# Design1.net
KiCad netlist of a schematic drawn in EAGLE
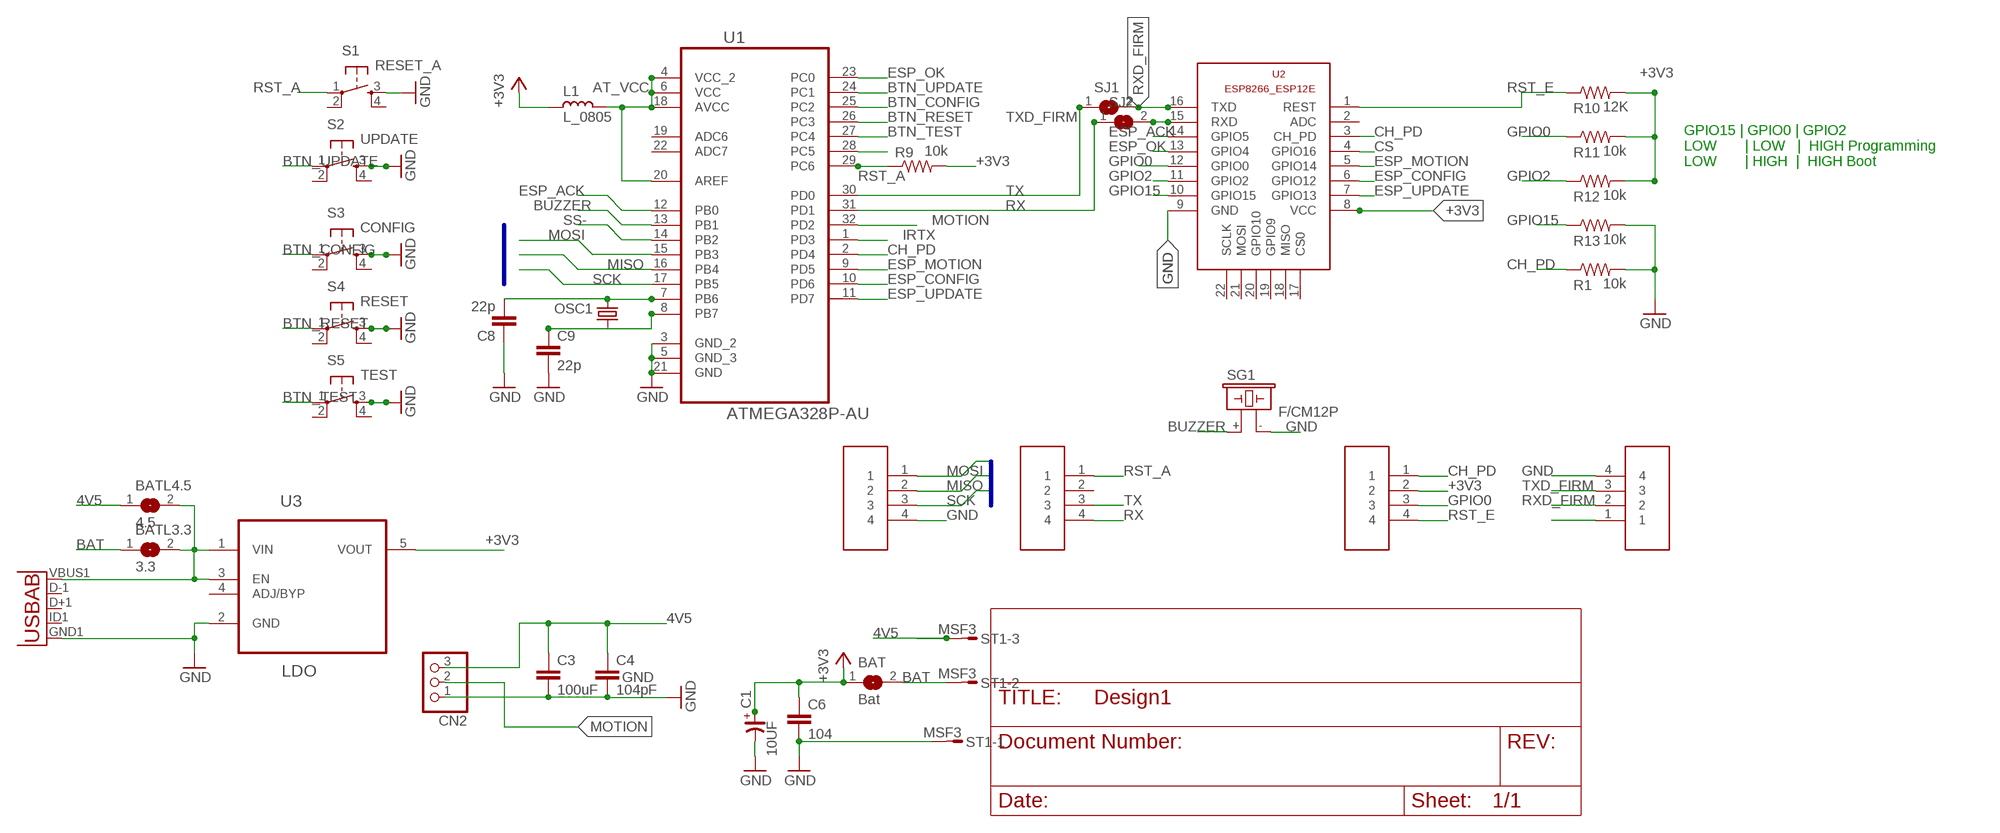
[diagram p0: schematic, sheet 1]

(export (version "E")
  (design (tool "Eeschema 10.0.6"))
  (components
    (comp (ref "BAT")
      (value "Bat")
      (footprint "eagle-import:SJ")
      (libsource (lib "eagle-import") (part "SJ"))
    )
    (comp (ref "BATL3.3")
      (value "3.3")
      (footprint "eagle-import:SJ")
      (libsource (lib "eagle-import") (part "SJ"))
    )
    (comp (ref "BATL4.5")
      (value "4.5")
      (footprint "eagle-import:SJ")
      (libsource (lib "eagle-import") (part "SJ"))
    )
    (comp (ref "C1")
      (value "10UF")
      (footprint "eagle-import:C6032_T")
      (libsource (lib "eagle-import") (part "CP_6032"))
    )
    (comp (ref "C3")
      (value "100uF")
      (footprint "eagle-import:C0805")
      (libsource (lib "eagle-import") (part "C-EUC0805"))
    )
    (comp (ref "C4")
      (value "104pF")
      (footprint "eagle-import:C0805")
      (libsource (lib "eagle-import") (part "C-EUC0805"))
    )
    (comp (ref "C6")
      (value "104")
      (footprint "eagle-import:C0805")
      (libsource (lib "eagle-import") (part "C-EUC0805"))
    )
    (comp (ref "C8")
      (value "22p")
      (footprint "eagle-import:C0805K")
      (libsource (lib "eagle-import") (part "C-EUC0805K"))
    )
    (comp (ref "C9")
      (value "22p")
      (footprint "eagle-import:C0805K")
      (libsource (lib "eagle-import") (part "C-EUC0805K"))
    )
    (comp (ref "CN1")
      (value "USB\"\"")
      (footprint "eagle-import:USB-MICRO-SMD")
      (libsource (lib "eagle-import") (part "USB{dblquote}{dblquote}"))
    )
    (comp (ref "CN2")
      (value "PINHD-1X3")
      (footprint "eagle-import:1X03")
      (libsource (lib "eagle-import") (part "PINHD-1X3"))
    )
    (comp (ref "CON1")
      (value "AT1")
      (footprint "eagle-import:FIRM_PADS")
      (libsource (lib "eagle-import") (part "FIRM_PADSSMD_FIRM_PADS"))
    )
    (comp (ref "CON2")
      (value "AT2")
      (footprint "eagle-import:FIRM_PADS")
      (libsource (lib "eagle-import") (part "FIRM_PADSSMD_FIRM_PADS"))
    )
    (comp (ref "CON3")
      (value "ESP1")
      (footprint "eagle-import:FIRM_PADS")
      (libsource (lib "eagle-import") (part "FIRM_PADSSMD_FIRM_PADS"))
    )
    (comp (ref "CON4")
      (value "ESP2")
      (footprint "eagle-import:FIRM_PADS")
      (libsource (lib "eagle-import") (part "FIRM_PADSSMD_FIRM_PADS"))
    )
    (comp (ref "L1")
      (value "L_0805")
      (footprint "eagle-import:L0805")
      (libsource (lib "eagle-import") (part "L_0805"))
    )
    (comp (ref "OSC1")
      (value "CRYSTALSM49")
      (footprint "eagle-import:SM49")
      (libsource (lib "eagle-import") (part "CRYSTALSM49"))
    )
    (comp (ref "R1")
      (value "10k")
      (footprint "eagle-import:0805")
      (libsource (lib "eagle-import") (part "0.75OHM-1/4W-1%(0805)"))
    )
    (comp (ref "R9")
      (value "10k")
      (footprint "eagle-import:0805")
      (libsource (lib "eagle-import") (part "0.75OHM-1/4W-1%(0805)"))
    )
    (comp (ref "R10")
      (value "12K")
      (footprint "eagle-import:0805")
      (libsource (lib "eagle-import") (part "0.75OHM-1/4W-1%(0805)"))
    )
    (comp (ref "R11")
      (value "10k")
      (footprint "eagle-import:0805")
      (libsource (lib "eagle-import") (part "0.75OHM-1/4W-1%(0805)"))
    )
    (comp (ref "R12")
      (value "10k")
      (footprint "eagle-import:0805")
      (libsource (lib "eagle-import") (part "0.75OHM-1/4W-1%(0805)"))
    )
    (comp (ref "R13")
      (value "10k")
      (footprint "eagle-import:0805")
      (libsource (lib "eagle-import") (part "0.75OHM-1/4W-1%(0805)"))
    )
    (comp (ref "S1")
      (value "RESET_A")
      (footprint "eagle-import:DTSM-6")
      (libsource (lib "eagle-import") (part "DTSM-6"))
    )
    (comp (ref "S2")
      (value "UPDATE")
      (footprint "eagle-import:DTSM-6")
      (libsource (lib "eagle-import") (part "DTSM-6"))
    )
    (comp (ref "S3")
      (value "CONFIG")
      (footprint "eagle-import:DTSM-6")
      (libsource (lib "eagle-import") (part "DTSM-6"))
    )
    (comp (ref "S4")
      (value "RESET")
      (footprint "eagle-import:DTSM-6")
      (libsource (lib "eagle-import") (part "DTSM-6"))
    )
    (comp (ref "S5")
      (value "TEST")
      (footprint "eagle-import:DTSM-6")
      (libsource (lib "eagle-import") (part "DTSM-6"))
    )
    (comp (ref "SG1")
      (value "F/CM12P")
      (footprint "eagle-import:F_CM12P")
      (libsource (lib "eagle-import") (part "F/CM12P"))
    )
    (comp (ref "SJ1") (value "SJ") (footprint "eagle-import:SJ") (libsource (lib "eagle-import") (part "SJ")))
    (comp (ref "SJ2") (value "SJ") (footprint "eagle-import:SJ") (libsource (lib "eagle-import") (part "SJ")))
    (comp (ref "ST1")
      (value "MSF3")
      (footprint "eagle-import:MSF3")
      (libsource (lib "eagle-import") (part "MSF3"))
    )
    (comp (ref "U1")
      (value "ATMEGA328P-AU")
      (footprint "eagle-import:QFP80P900X900X120-32N")
      (libsource (lib "eagle-import") (part "ATMEGA328P-AU"))
    )
    (comp (ref "U2")
      (value "ESP8266-12EESP8266-ESP12E")
      (footprint "eagle-import:ESP8266-ESP12E")
      (libsource (lib "eagle-import") (part "ESP8266-12EESP8266-ESP12E"))
    )
    (comp (ref "U3")
      (value "LDO")
      (footprint "eagle-import:SOT95P280X145-5N")
      (libsource (lib "eagle-import") (part "SPX3819M5-L-3-3"))
    )
  )
  (nets
    (net (code "2") (name "+3V3") (class "Default")
      (node (ref "BAT") (pin "1") (pinfunction "1_1") (pintype "passive"))
      (node (ref "C1") (pin "+") (pinfunction "+_+") (pintype "passive"))
      (node (ref "C6") (pin "1") (pinfunction "1_1") (pintype "passive"))
      (node (ref "CON3") (pin "2") (pinfunction "2_2") (pintype "bidirectional"))
      (node (ref "L1") (pin "2") (pinfunction "2_2") (pintype "passive"))
      (node (ref "R10") (pin "2") (pinfunction "2_2") (pintype "passive"))
      (node (ref "R11") (pin "2") (pinfunction "2_2") (pintype "passive"))
      (node (ref "R12") (pin "2") (pinfunction "2_2") (pintype "passive"))
      (node (ref "R9") (pin "2") (pinfunction "2_2") (pintype "passive"))
      (node (ref "U2") (pin "8") (pinfunction "VCC_8") (pintype "bidirectional"))
      (node (ref "U3") (pin "5") (pinfunction "VOUT_5") (pintype "output"))
    )
    (net (code "3") (name "/4V5") (class "Default")
      (node (ref "BATL4.5") (pin "1") (pinfunction "1_1") (pintype "passive"))
      (node (ref "C3") (pin "1") (pinfunction "1_1") (pintype "passive"))
      (node (ref "C4") (pin "1") (pinfunction "1_1") (pintype "passive"))
      (node (ref "CN2") (pin "3") (pinfunction "3_3") (pintype "passive"))
      (node (ref "ST1") (pin "3") (pinfunction "S_3") (pintype "passive"))
    )
    (net (code "4") (name "/AT_VCC") (class "Default")
      (node (ref "L1") (pin "1") (pinfunction "1_1") (pintype "passive"))
      (node (ref "U1") (pin "18") (pinfunction "AVCC_18") (pintype "power_in"))
      (node (ref "U1") (pin "20") (pinfunction "AREF_20") (pintype "input"))
      (node (ref "U1") (pin "4") (pinfunction "VCC_2_4") (pintype "power_in"))
      (node (ref "U1") (pin "6") (pinfunction "VCC_6") (pintype "power_in"))
    )
    (net (code "5") (name "/BAT") (class "Default")
      (node (ref "BAT") (pin "2") (pinfunction "2_2") (pintype "passive"))
      (node (ref "BATL3.3") (pin "1") (pinfunction "1_1") (pintype "passive"))
      (node (ref "ST1") (pin "2") (pinfunction "S_2") (pintype "passive"))
    )
    (net (code "6") (name "/BTN_CONFIG") (class "Default")
      (node (ref "S3") (pin "1") (pinfunction "1_1") (pintype "passive"))
      (node (ref "U1") (pin "25") (pinfunction "PC2_25") (pintype "bidirectional"))
    )
    (net (code "7") (name "/BTN_RESET") (class "Default")
      (node (ref "S4") (pin "1") (pinfunction "1_1") (pintype "passive"))
      (node (ref "U1") (pin "26") (pinfunction "PC3_26") (pintype "bidirectional"))
    )
    (net (code "8") (name "/BTN_TEST") (class "Default")
      (node (ref "S5") (pin "1") (pinfunction "1_1") (pintype "passive"))
      (node (ref "U1") (pin "27") (pinfunction "PC4_27") (pintype "bidirectional"))
    )
    (net (code "9") (name "/BTN_UPDATE") (class "Default")
      (node (ref "S2") (pin "1") (pinfunction "1_1") (pintype "passive"))
      (node (ref "U1") (pin "24") (pinfunction "PC1_24") (pintype "bidirectional"))
    )
    (net (code "10") (name "/BUZZER") (class "Default")
      (node (ref "SG1") (pin "+") (pinfunction "1_+") (pintype "passive"))
      (node (ref "U1") (pin "13") (pinfunction "PB1_13") (pintype "bidirectional"))
    )
    (net (code "11") (name "/CH_PD") (class "Default")
      (node (ref "CON3") (pin "1") (pinfunction "1_1") (pintype "bidirectional"))
      (node (ref "R1") (pin "1") (pinfunction "1_1") (pintype "passive"))
      (node (ref "U1") (pin "2") (pinfunction "PD4_2") (pintype "bidirectional"))
      (node (ref "U2") (pin "3") (pinfunction "CH_PD_3") (pintype "bidirectional"))
    )
    (net (code "12") (name "/CS") (class "Default")
      (node (ref "U2") (pin "4") (pinfunction "GPIO16_4") (pintype "bidirectional"))
    )
    (net (code "13") (name "/ESP_ACK") (class "Default")
      (node (ref "U1") (pin "12") (pinfunction "PB0_12") (pintype "bidirectional"))
      (node (ref "U2") (pin "14") (pinfunction "GPIO5_14") (pintype "bidirectional"))
    )
    (net (code "14") (name "/ESP_CONFIG") (class "Default")
      (node (ref "U1") (pin "10") (pinfunction "PD6_10") (pintype "bidirectional"))
      (node (ref "U2") (pin "6") (pinfunction "GPIO12_6") (pintype "bidirectional"))
    )
    (net (code "15") (name "/ESP_MOTION") (class "Default")
      (node (ref "U1") (pin "9") (pinfunction "PD5_9") (pintype "bidirectional"))
      (node (ref "U2") (pin "5") (pinfunction "GPIO14_5") (pintype "bidirectional"))
    )
    (net (code "16") (name "/ESP_OK") (class "Default")
      (node (ref "U1") (pin "23") (pinfunction "PC0_23") (pintype "bidirectional"))
      (node (ref "U2") (pin "13") (pinfunction "GPIO4_13") (pintype "bidirectional"))
    )
    (net (code "17") (name "/ESP_UPDATE") (class "Default")
      (node (ref "U1") (pin "11") (pinfunction "PD7_11") (pintype "bidirectional"))
      (node (ref "U2") (pin "7") (pinfunction "GPIO13_7") (pintype "bidirectional"))
    )
    (net (code "18") (name "/GPIO0") (class "Default")
      (node (ref "CON3") (pin "3") (pinfunction "3_3") (pintype "bidirectional"))
      (node (ref "R11") (pin "1") (pinfunction "1_1") (pintype "passive"))
      (node (ref "U2") (pin "12") (pinfunction "GPIO0_12") (pintype "bidirectional"))
    )
    (net (code "19") (name "/GPIO2") (class "Default")
      (node (ref "R12") (pin "1") (pinfunction "1_1") (pintype "passive"))
      (node (ref "U2") (pin "11") (pinfunction "GPIO2_11") (pintype "bidirectional"))
    )
    (net (code "20") (name "/GPIO15") (class "Default")
      (node (ref "R13") (pin "1") (pinfunction "1_1") (pintype "passive"))
      (node (ref "U2") (pin "10") (pinfunction "GPIO15_10") (pintype "bidirectional"))
    )
    (net (code "21") (name "/IRTX") (class "Default")
      (node (ref "U1") (pin "1") (pinfunction "PD3_1") (pintype "bidirectional"))
    )
    (net (code "22") (name "/ISP") (class "Default")
      (node (ref "CON1") (pin "1") (pinfunction "1_1") (pintype "bidirectional"))
      (node (ref "U1") (pin "15") (pinfunction "PB3_15") (pintype "bidirectional"))
    )
    (net (code "23") (name "/MISO") (class "Default")
      (node (ref "CON1") (pin "2") (pinfunction "2_2") (pintype "bidirectional"))
      (node (ref "U1") (pin "16") (pinfunction "PB4_16") (pintype "bidirectional"))
    )
    (net (code "24") (name "/RST_A") (class "Default")
      (node (ref "CON2") (pin "1") (pinfunction "1_1") (pintype "bidirectional"))
      (node (ref "R9") (pin "1") (pinfunction "1_1") (pintype "passive"))
      (node (ref "S1") (pin "1") (pinfunction "1_1") (pintype "passive"))
      (node (ref "U1") (pin "29") (pinfunction "PC6_29") (pintype "bidirectional"))
    )
    (net (code "25") (name "/RST_E") (class "Default")
      (node (ref "CON3") (pin "4") (pinfunction "4_4") (pintype "bidirectional"))
      (node (ref "R10") (pin "1") (pinfunction "1_1") (pintype "passive"))
      (node (ref "U2") (pin "1") (pinfunction "REST_1") (pintype "bidirectional"))
    )
    (net (code "26") (name "/RX") (class "Default")
      (node (ref "CON2") (pin "4") (pinfunction "4_4") (pintype "bidirectional"))
      (node (ref "SJ2") (pin "1") (pinfunction "1_1") (pintype "passive"))
      (node (ref "U1") (pin "31") (pinfunction "PD1_31") (pintype "bidirectional"))
    )
    (net (code "27") (name "/SCK") (class "Default")
      (node (ref "CON1") (pin "3") (pinfunction "3_3") (pintype "bidirectional"))
      (node (ref "U1") (pin "17") (pinfunction "PB5_17") (pintype "bidirectional"))
    )
    (net (code "28") (name "/SS-") (class "Default")
      (node (ref "U1") (pin "14") (pinfunction "PB2_14") (pintype "bidirectional"))
    )
    (net (code "29") (name "/TX") (class "Default")
      (node (ref "CON2") (pin "3") (pinfunction "3_3") (pintype "bidirectional"))
      (node (ref "SJ1") (pin "1") (pinfunction "1_1") (pintype "passive"))
      (node (ref "U1") (pin "30") (pinfunction "PD0_30") (pintype "bidirectional"))
    )
    (net (code "30") (name "/TXD_FIRM") (class "Default")
      (node (ref "CON4") (pin "3") (pinfunction "3_3") (pintype "bidirectional"))
      (node (ref "SJ2") (pin "2") (pinfunction "2_2") (pintype "passive"))
      (node (ref "U2") (pin "15") (pinfunction "RXD_15") (pintype "bidirectional"))
    )
    (net (code "32") (name "GND") (class "Default")
      (node (ref "C1") (pin "-") (pinfunction "-_-") (pintype "passive"))
      (node (ref "C3") (pin "2") (pinfunction "2_2") (pintype "passive"))
      (node (ref "C4") (pin "2") (pinfunction "2_2") (pintype "passive"))
      (node (ref "C6") (pin "2") (pinfunction "2_2") (pintype "passive"))
      (node (ref "C8") (pin "1") (pinfunction "1_1") (pintype "passive"))
      (node (ref "C9") (pin "2") (pinfunction "2_2") (pintype "passive"))
      (node (ref "CN1") (pin "GND1") (pinfunction "GND_GND1") (pintype "bidirectional"))
      (node (ref "CN2") (pin "1") (pinfunction "1_1") (pintype "passive"))
      (node (ref "CON1") (pin "4") (pinfunction "4_4") (pintype "bidirectional"))
      (node (ref "CON4") (pin "4") (pinfunction "4_4") (pintype "bidirectional"))
      (node (ref "R1") (pin "2") (pinfunction "2_2") (pintype "passive"))
      (node (ref "R13") (pin "2") (pinfunction "2_2") (pintype "passive"))
      (node (ref "S1") (pin "3") (pinfunction "3_3") (pintype "passive"))
      (node (ref "S2") (pin "3") (pinfunction "3_3") (pintype "passive"))
      (node (ref "S3") (pin "3") (pinfunction "3_3") (pintype "passive"))
      (node (ref "S4") (pin "3") (pinfunction "3_3") (pintype "passive"))
      (node (ref "S5") (pin "3") (pinfunction "3_3") (pintype "passive"))
      (node (ref "SG1") (pin "-") (pinfunction "2_-") (pintype "passive"))
      (node (ref "ST1") (pin "1") (pinfunction "S_1") (pintype "passive"))
      (node (ref "U1") (pin "21") (pinfunction "GND_21") (pintype "passive"))
      (node (ref "U1") (pin "3") (pinfunction "GND_2_3") (pintype "passive"))
      (node (ref "U1") (pin "5") (pinfunction "GND_3_5") (pintype "passive"))
      (node (ref "U2") (pin "9") (pinfunction "GND_9") (pintype "bidirectional"))
      (node (ref "U3") (pin "2") (pinfunction "GND_2") (pintype "passive"))
    )
    (net (code "33") (name "MOTION") (class "Default")
      (node (ref "CN2") (pin "2") (pinfunction "2_2") (pintype "passive"))
      (node (ref "U1") (pin "32") (pinfunction "PD2_32") (pintype "bidirectional"))
    )
    (net (code "34") (name "Net-(CN1-VBUS)") (class "Default")
      (node (ref "BATL3.3") (pin "2") (pinfunction "2_2") (pintype "passive"))
      (node (ref "BATL4.5") (pin "2") (pinfunction "2_2") (pintype "passive"))
      (node (ref "CN1") (pin "VBUS1") (pinfunction "VBUS_VBUS1") (pintype "bidirectional"))
      (node (ref "U3") (pin "1") (pinfunction "VIN_1") (pintype "power_in"))
      (node (ref "U3") (pin "3") (pinfunction "EN_3") (pintype "input"))
    )
    (net (code "35") (name "Net-(U1-PB6)") (class "Default")
      (node (ref "C8") (pin "2") (pinfunction "2_2") (pintype "passive"))
      (node (ref "OSC1") (pin "1") (pinfunction "1_1") (pintype "passive"))
      (node (ref "U1") (pin "7") (pinfunction "PB6_7") (pintype "bidirectional"))
    )
    (net (code "36") (name "Net-(U1-PB7)") (class "Default")
      (node (ref "C9") (pin "1") (pinfunction "1_1") (pintype "passive"))
      (node (ref "OSC1") (pin "2") (pinfunction "2_2") (pintype "passive"))
      (node (ref "U1") (pin "8") (pinfunction "PB7_8") (pintype "bidirectional"))
    )
    (net (code "37") (name "RXD_FIRM") (class "Default")
      (node (ref "CON4") (pin "2") (pinfunction "2_2") (pintype "bidirectional"))
      (node (ref "SJ1") (pin "2") (pinfunction "2_2") (pintype "passive"))
      (node (ref "U2") (pin "16") (pinfunction "TXD_16") (pintype "bidirectional"))
    )
    (net (code "38") (name "unconnected-(CN1-D+-PadD+1)") (class "Default")
      (node (ref "CN1") (pin "D+1") (pinfunction "D+_D+1") (pintype "bidirectional"))
    )
    (net (code "39") (name "unconnected-(CN1-D--PadD-1)") (class "Default")
      (node (ref "CN1") (pin "D-1") (pinfunction "D-_D-1") (pintype "bidirectional"))
    )
    (net (code "40") (name "unconnected-(CN1-USBID-PadID1)") (class "Default")
      (node (ref "CN1") (pin "ID1") (pinfunction "USBID_ID1") (pintype "bidirectional"))
    )
    (net (code "41") (name "unconnected-(CON2-Pad2)") (class "Default")
      (node (ref "CON2") (pin "2") (pinfunction "2_2") (pintype "bidirectional"))
    )
    (net (code "42") (name "unconnected-(CON4-Pad1)") (class "Default")
      (node (ref "CON4") (pin "1") (pinfunction "1_1") (pintype "bidirectional"))
    )
    (net (code "43") (name "unconnected-(S1-Pad2)") (class "Default")
      (node (ref "S1") (pin "2") (pinfunction "2_2") (pintype "passive"))
    )
    (net (code "44") (name "unconnected-(S1-Pad4)") (class "Default")
      (node (ref "S1") (pin "4") (pinfunction "4_4") (pintype "passive"))
    )
    (net (code "45") (name "unconnected-(S2-Pad2)") (class "Default")
      (node (ref "S2") (pin "2") (pinfunction "2_2") (pintype "passive"))
    )
    (net (code "46") (name "unconnected-(S2-Pad4)") (class "Default")
      (node (ref "S2") (pin "4") (pinfunction "4_4") (pintype "passive"))
    )
    (net (code "47") (name "unconnected-(S3-Pad2)") (class "Default")
      (node (ref "S3") (pin "2") (pinfunction "2_2") (pintype "passive"))
    )
    (net (code "48") (name "unconnected-(S3-Pad4)") (class "Default")
      (node (ref "S3") (pin "4") (pinfunction "4_4") (pintype "passive"))
    )
    (net (code "49") (name "unconnected-(S4-Pad2)") (class "Default")
      (node (ref "S4") (pin "2") (pinfunction "2_2") (pintype "passive"))
    )
    (net (code "50") (name "unconnected-(S4-Pad4)") (class "Default")
      (node (ref "S4") (pin "4") (pinfunction "4_4") (pintype "passive"))
    )
    (net (code "51") (name "unconnected-(S5-Pad2)") (class "Default")
      (node (ref "S5") (pin "2") (pinfunction "2_2") (pintype "passive"))
    )
    (net (code "52") (name "unconnected-(S5-Pad4)") (class "Default")
      (node (ref "S5") (pin "4") (pinfunction "4_4") (pintype "passive"))
    )
    (net (code "53") (name "unconnected-(U1-ADC6-Pad19)") (class "Default")
      (node (ref "U1") (pin "19") (pinfunction "ADC6_19") (pintype "input"))
    )
    (net (code "54") (name "unconnected-(U1-ADC7-Pad22)") (class "Default")
      (node (ref "U1") (pin "22") (pinfunction "ADC7_22") (pintype "input"))
    )
    (net (code "55") (name "unconnected-(U1-PC5-Pad28)") (class "Default")
      (node (ref "U1") (pin "28") (pinfunction "PC5_28") (pintype "bidirectional"))
    )
    (net (code "56") (name "unconnected-(U2-ADC-Pad2)") (class "Default")
      (node (ref "U2") (pin "2") (pinfunction "ADC_2") (pintype "bidirectional"))
    )
    (net (code "57") (name "unconnected-(U2-CS0-Pad17)") (class "Default")
      (node (ref "U2") (pin "17") (pinfunction "CS0_17") (pintype "bidirectional"))
    )
    (net (code "58") (name "unconnected-(U2-GPIO9-Pad19)") (class "Default")
      (node (ref "U2") (pin "19") (pinfunction "GPIO9_19") (pintype "bidirectional"))
    )
    (net (code "59") (name "unconnected-(U2-GPIO10-Pad20)") (class "Default")
      (node (ref "U2") (pin "20") (pinfunction "GPIO10_20") (pintype "bidirectional"))
    )
    (net (code "60") (name "unconnected-(U2-MISO-Pad18)") (class "Default")
      (node (ref "U2") (pin "18") (pinfunction "MISO_18") (pintype "bidirectional"))
    )
    (net (code "61") (name "unconnected-(U2-MOSI-Pad21)") (class "Default")
      (node (ref "U2") (pin "21") (pinfunction "MOSI_21") (pintype "bidirectional"))
    )
    (net (code "62") (name "unconnected-(U2-SCLK-Pad22)") (class "Default")
      (node (ref "U2") (pin "22") (pinfunction "SCLK_22") (pintype "bidirectional"))
    )
    (net (code "63") (name "unconnected-(U3-ADJ{slash}BYP-Pad4)") (class "Default")
      (node (ref "U3") (pin "4") (pinfunction "ADJ/BYP_4") (pintype "passive"))
    )
  )
)
